# Sheet1.net
KiCad netlist of a schematic drawn in Altium Designer
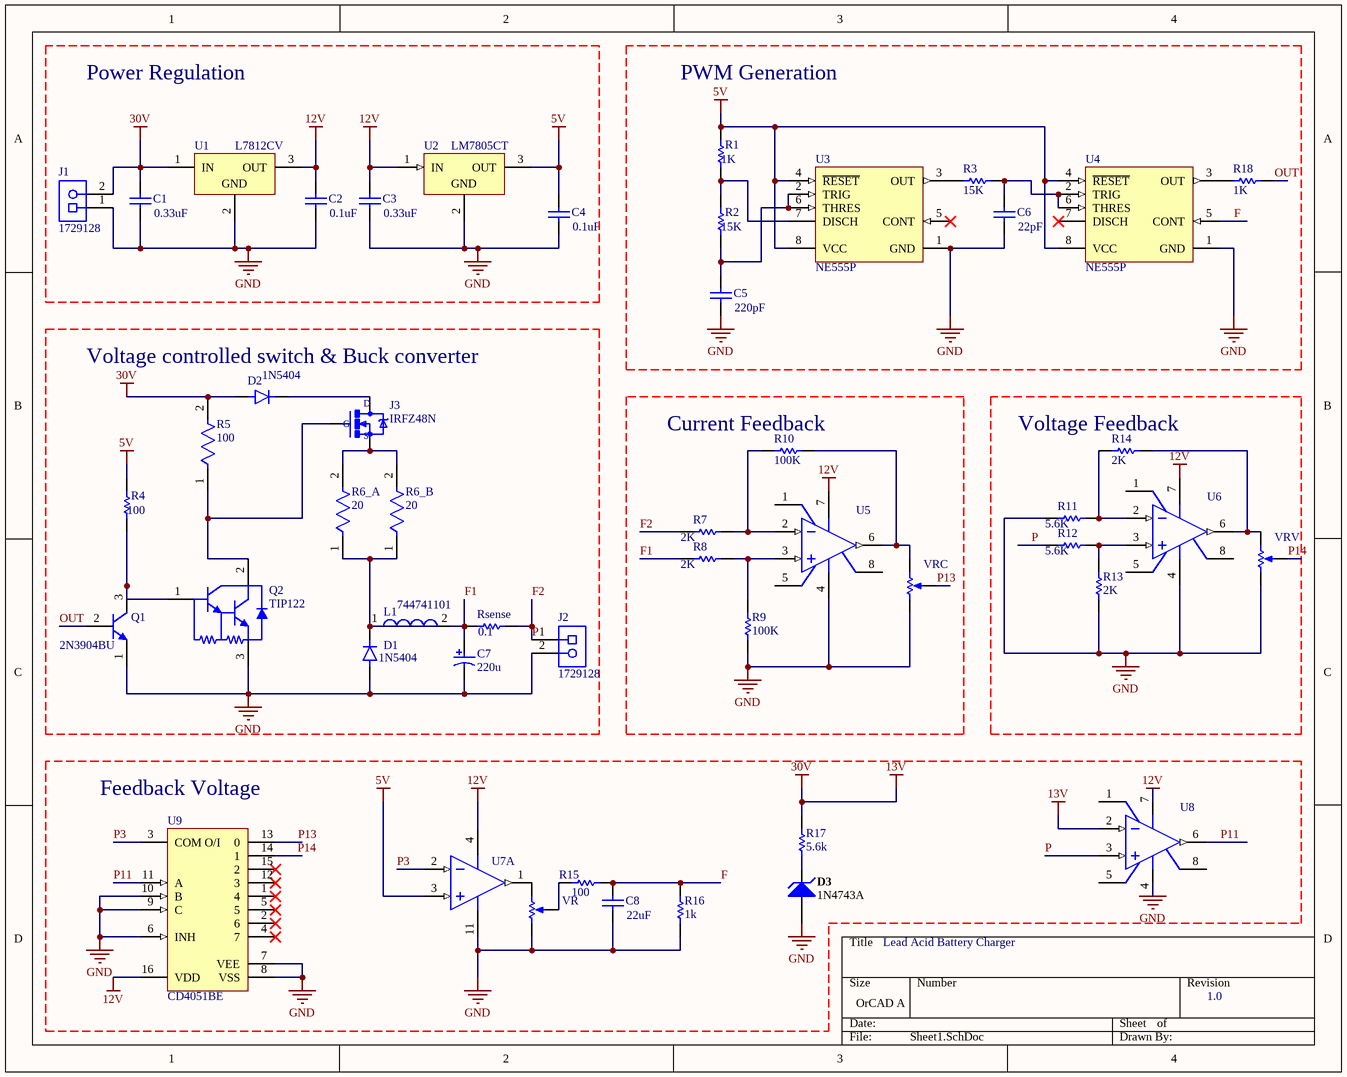
[diagram p0: Sheet1.SchDoc]

(export (version "E")
  (design (tool "Eeschema 10.0.6"))
  (components
    (comp (ref "C1")
      (value "0.33uF")
      (footprint "RAD-0.3")
      (description "Capacitor")
      (fields (field (name "Comment") "Cap") (field (name "PUBLISHER") "Altium Limited"))
      (libsource (lib "Miscellaneous Devices") (part "Cap"))
    )
    (comp (ref "C2")
      (value "0.1uF")
      (footprint "RAD-0.3")
      (description "Capacitor")
      (fields (field (name "Comment") "Cap") (field (name "PUBLISHER") "Altium Limited"))
      (libsource (lib "Miscellaneous Devices") (part "Cap"))
    )
    (comp (ref "C3")
      (value "0.33uF")
      (footprint "RAD-0.3")
      (description "Capacitor")
      (fields (field (name "Comment") "Cap") (field (name "PUBLISHER") "Altium Limited"))
      (libsource (lib "Miscellaneous Devices") (part "Cap"))
    )
    (comp (ref "C4")
      (value "0.1uF")
      (footprint "RAD-0.3")
      (description "Capacitor")
      (fields (field (name "Comment") "Cap") (field (name "PUBLISHER") "Altium Limited"))
      (libsource (lib "Miscellaneous Devices") (part "Cap"))
    )
    (comp (ref "C5")
      (value "220pF")
      (footprint "RAD-0.3")
      (description "Capacitor")
      (fields (field (name "Comment") "Cap") (field (name "PUBLISHER") "Altium Limited"))
      (libsource (lib "Miscellaneous Devices") (part "Cap"))
    )
    (comp (ref "C6")
      (value "22pF")
      (footprint "RAD-0.3")
      (description "Capacitor")
      (fields (field (name "Comment") "Cap") (field (name "PUBLISHER") "Altium Limited"))
      (libsource (lib "Miscellaneous Devices") (part "Cap"))
    )
    (comp (ref "C7")
      (value "220u")
      (footprint "PNSC-ECA-1VM221-2")
      (description "Aluminum Electrolytic Capacitor, 220 uF, +/- 20%, 35 V, -40 to 85 degC, 2-Pin THD, RoHS, Bulk")
      (fields (field (name "MANUFACTURER") "Panasonic"))
      (libsource (lib "Altium Content Vault") (part "CAP-P-2"))
    )
    (comp (ref "C8")
      (value "22uF")
      (footprint "RAD-0.3")
      (description "Capacitor")
      (fields (field (name "Comment") "Cap") (field (name "PUBLISHER") "Altium Limited"))
      (libsource (lib "Miscellaneous Devices") (part "Cap"))
    )
    (comp (ref "D1")
      (value "1N5404")
      (footprint "DIOAD1990W125L900D530")
      (fields (field (name "MP") "1N5404RL") (field (name "MF") "{'manufacturer': u'ON Semiconductor'}"))
      (libsource (lib "SnapEDA_Library") (part "1N5404RL"))
    )
    (comp (ref "D2")
      (value "1N5404")
      (footprint "DIOAD1990W125L900D530")
      (fields (field (name "MP") "1N5404RL") (field (name "MF") "{'manufacturer': u'ON Semiconductor'}"))
      (libsource (lib "SnapEDA_Library") (part "1N5404RL"))
    )
    (comp (ref "D3")
      (value "1N4743A")
      (footprint "FAIR-DO-41-2_V")
      (description "Zener Diode, 13V, 1W, 5%, -65 to 200 degC, 2-Pin DO-41, Body 2.72 x 5.2 mm, RoHS")
      (fields (field (name "MANUFACTURER") "Fairchild Semiconductor") (field (name "TOLERANCE") "5%"))
      (libsource (lib "Altium Content Vault") (part "FAIR-DZEN-A1K2-2"))
    )
    (comp (ref "J1")
      (value "1729128")
      (footprint "PHOE-1729128-2_V")
      (description "PCB Terminal Block, 13.5 A, 400 V, 2-Pin THD, RoHS, Bulk")
      (fields (field (name "MANUFACTURER") "Phoenix Contact"))
      (libsource (lib "") (part "CN-2P-F-R2_1"))
    )
    (comp (ref "J2")
      (value "1729128")
      (footprint "PHOE-1729128-2_V")
      (description "PCB Terminal Block, 13.5 A, 400 V, 2-Pin THD, RoHS, Bulk")
      (fields (field (name "MANUFACTURER") "Phoenix Contact"))
      (libsource (lib "Altium Content Vault") (part "CN-2P-F-R2"))
    )
    (comp (ref "J3")
      (value "IRFZ48N")
      (footprint "IRFZ44NPBF:TO-220")
      (fields (field (name "MF") "{'manufacturer': u'Infineon'}") (field (name "MP") "IRFZ44NPBF"))
      (libsource (lib "*") (part "IRFZ44NPBF"))
    )
    (comp (ref "L1")
      (value "744741101")
      (footprint "WE-TI-LS")
      (description "Radial Leaded Wire Wound Inductor WE-TI, L = 100 µH")
      (libsource (lib "Altium Content Vault") (part "PAS-IND-INDUCTOR-2"))
    )
    (comp (ref "Q1")
      (value "2N3904BU")
      (footprint "FAIR-TO-92")
      (description "NPN General-Purpose Amplifier, 40 V VCEO, 0.2 A, -55 to 150 degC, 2-Pin TO-92, RoHS, Bulk")
      (fields (field (name "MANUFACTURER") "FairchildSemiconductor"))
      (libsource (lib "Altium Content Vault") (part "NPN-E1B2C3-3"))
    )
    (comp (ref "Q2")
      (value "TIP122")
      (footprint "ONSC-TO-220-3-221A-09")
      (description "Plastic Medium-Power, Complementary Silicon Transistor, 3-Pin TO-220, Tube")
      (fields (field (name "MANUFACTURER") "On Semiconductor"))
      (libsource (lib "Altium Content Vault") (part "ONSC-DT-NPN-B1C2E3-3_A"))
    )
    (comp (ref "R1")
      (value "1K")
      (footprint "AXIAL-0.3")
      (description "Resistor")
      (fields (field (name "Comment") "Res1") (field (name "PUBLISHER") "Altium Limited"))
      (libsource (lib "Miscellaneous Devices") (part "Res1"))
    )
    (comp (ref "R2")
      (value "15K")
      (footprint "AXIAL-0.3")
      (description "Resistor")
      (fields (field (name "Comment") "Res1") (field (name "PUBLISHER") "Altium Limited"))
      (libsource (lib "Miscellaneous Devices") (part "Res1"))
    )
    (comp (ref "R3")
      (value "15K")
      (footprint "AXIAL-0.3")
      (description "Resistor")
      (fields (field (name "Comment") "Res1") (field (name "PUBLISHER") "Altium Limited"))
      (libsource (lib "Miscellaneous Devices") (part "Res1"))
    )
    (comp (ref "R4")
      (value "100")
      (footprint "AXIAL-0.3")
      (description "Resistor")
      (fields (field (name "Comment") "Res1") (field (name "PUBLISHER") "Altium Limited"))
      (libsource (lib "Miscellaneous Devices") (part "Res1"))
    )
    (comp (ref "R5")
      (value "100")
      (footprint "FP-SQP500-MFG")
      (description "RES 1.2 OHM 5W 5% AXIAL")
      (fields
        (field (name "MANUFACTURER PART NUMBER") "SQP500JB-1R2")
        (field (name "OCTOPART") "https://octopart.com/sqp500jb-1r2-yageo-1162571")
      )
      (libsource (lib "Altium Content Vault") (part "1029c3af85768c4190bb7ad29bc67b5"))
    )
    (comp (ref "R6_A")
      (value "20")
      (footprint "FP-SQP500-MFG")
      (description "RES 1.2 OHM 5W 5% AXIAL")
      (fields
        (field (name "MANUFACTURER PART NUMBER") "SQP500JB-1R2")
        (field (name "OCTOPART") "https://octopart.com/sqp500jb-1r2-yageo-1162571")
      )
      (libsource (lib "Altium Content Vault") (part "1029c3af85768c4190bb7ad29bc67b5"))
    )
    (comp (ref "R6_B")
      (value "20")
      (footprint "FP-SQP500-MFG")
      (description "RES 1.2 OHM 5W 5% AXIAL")
      (fields
        (field (name "MANUFACTURER PART NUMBER") "SQP500JB-1R2")
        (field (name "OCTOPART") "https://octopart.com/sqp500jb-1r2-yageo-1162571")
      )
      (libsource (lib "Altium Content Vault") (part "1029c3af85768c4190bb7ad29bc67b5"))
    )
    (comp (ref "R7")
      (value "2K")
      (footprint "AXIAL-0.3")
      (description "Resistor")
      (fields (field (name "Comment") "Res1") (field (name "PUBLISHER") "Altium Limited"))
      (libsource (lib "Miscellaneous Devices") (part "Res1"))
    )
    (comp (ref "R8")
      (value "2K")
      (footprint "AXIAL-0.3")
      (description "Resistor")
      (fields (field (name "Comment") "Res1") (field (name "PUBLISHER") "Altium Limited"))
      (libsource (lib "Miscellaneous Devices") (part "Res1"))
    )
    (comp (ref "R9")
      (value "100K")
      (footprint "AXIAL-0.3")
      (description "Resistor")
      (fields (field (name "Comment") "Res1") (field (name "PUBLISHER") "Altium Limited"))
      (libsource (lib "Miscellaneous Devices") (part "Res1"))
    )
    (comp (ref "R10")
      (value "100K")
      (footprint "AXIAL-0.3")
      (description "Resistor")
      (fields (field (name "Comment") "Res1") (field (name "PUBLISHER") "Altium Limited"))
      (libsource (lib "Miscellaneous Devices") (part "Res1"))
    )
    (comp (ref "R11")
      (value "5.6K")
      (footprint "AXIAL-0.3")
      (description "Resistor")
      (fields (field (name "Comment") "Res1") (field (name "PUBLISHER") "Altium Limited"))
      (libsource (lib "Miscellaneous Devices") (part "Res1"))
    )
    (comp (ref "R12")
      (value "5.6K")
      (footprint "AXIAL-0.3")
      (description "Resistor")
      (fields (field (name "Comment") "Res1") (field (name "PUBLISHER") "Altium Limited"))
      (libsource (lib "Miscellaneous Devices") (part "Res1"))
    )
    (comp (ref "R13")
      (value "2K")
      (footprint "AXIAL-0.3")
      (description "Resistor")
      (fields (field (name "Comment") "Res1") (field (name "PUBLISHER") "Altium Limited"))
      (libsource (lib "Miscellaneous Devices") (part "Res1"))
    )
    (comp (ref "R14")
      (value "2K")
      (footprint "AXIAL-0.3")
      (description "Resistor")
      (fields (field (name "Comment") "Res1") (field (name "PUBLISHER") "Altium Limited"))
      (libsource (lib "Miscellaneous Devices") (part "Res1"))
    )
    (comp (ref "R15")
      (value "100")
      (footprint "AXIAL-0.3")
      (description "Resistor")
      (fields (field (name "Comment") "Res1") (field (name "PUBLISHER") "Altium Limited"))
      (libsource (lib "Miscellaneous Devices") (part "Res1"))
    )
    (comp (ref "R16")
      (value "1k")
      (footprint "AXIAL-0.3")
      (description "Resistor")
      (fields (field (name "Comment") "Res1") (field (name "PUBLISHER") "Altium Limited"))
      (libsource (lib "Miscellaneous Devices") (part "Res1"))
    )
    (comp (ref "R17")
      (value "5.6k")
      (footprint "AXIAL-0.3")
      (description "Resistor")
      (fields (field (name "Comment") "Res1") (field (name "PUBLISHER") "Altium Limited"))
      (libsource (lib "Miscellaneous Devices") (part "Res1"))
    )
    (comp (ref "R18")
      (value "1K")
      (footprint "AXIAL-0.3")
      (description "Resistor")
      (fields (field (name "Comment") "Res1") (field (name "PUBLISHER") "Altium Limited"))
      (libsource (lib "Miscellaneous Devices") (part "Res1"))
    )
    (comp (ref "Rsense")
      (value "0.1")
      (footprint "AXIAL-0.3")
      (description "Resistor")
      (fields (field (name "Comment") "Res1") (field (name "PUBLISHER") "Altium Limited"))
      (libsource (lib "Miscellaneous Devices") (part "Res1"))
    )
    (comp (ref "U1")
      (value "L7812CV")
      (footprint "TO220")
      (description "Positive Voltage Regulator, 12V, 3-Pin TO-220")
      (libsource (lib "Altium Content Vault") (part "PM-REG-L4940-SIL3"))
    )
    (comp (ref "U2")
      (value "LM7805CT")
      (footprint "FAIR-TO-220-3")
      (description "Positive Voltage Regulator, 5 V, 1 A, -40 to 125 degC, 3-Pin TO-220, RoHS, Tube")
      (fields (field (name "MANUFACTURER") "FairchildSemiconductor"))
      (libsource (lib "Altium Content Vault") (part "FAIR-LM7805CT-TO220-3"))
    )
    (comp (ref "U3")
      (value "NE555P")
      (footprint "P0008A")
      (description "Precision Timer, 4.5 to 16 V, 0 to 70 degC, 8-Pin DIP, Pb-Free, Tube")
      (fields (field (name "MANUFACTURER") "TexasInstruments"))
      (libsource (lib "Altium Content Vault") (part "TI-NE555-P8"))
    )
    (comp (ref "U4")
      (value "NE555P")
      (footprint "P0008A")
      (description "Precision Timer, 4.5 to 16 V, 0 to 70 degC, 8-Pin DIP, Pb-Free, Tube")
      (fields (field (name "MANUFACTURER") "TexasInstruments"))
      (libsource (lib "Altium Content Vault") (part "TI-NE555-P8"))
    )
    (comp (ref "U5")
      (value "LM741CN/NOPB")
      (footprint "P0008A")
      (description "Operational Amplifier, 8-pin MDIP, Pb-Free")
      (fields (field (name "MANUFACTURER") "Texas Instruments"))
      (libsource (lib "Altium Content Vault") (part "AMP-OPA-LM741-8"))
    )
    (comp (ref "U6")
      (value "LM741CN/NOPB")
      (footprint "P0008A")
      (description "Operational Amplifier, 8-pin MDIP, Pb-Free")
      (fields (field (name "MANUFACTURER") "Texas Instruments"))
      (libsource (lib "Altium Content Vault") (part "AMP-OPA-LM741-8"))
    )
    (comp (ref "U7")
      (value "TL074ACN")
      (footprint "N0014A")
      (fields (field (name "MANUFACTURER") "Texas Instruments"))
      (libsource (lib "Altium Content Vault") (part "TI-TL074X-14"))
    )
    (comp (ref "U8")
      (value "LM741CN/NOPB")
      (footprint "P0008A")
      (description "Operational Amplifier, 8-pin MDIP, Pb-Free")
      (fields (field (name "MANUFACTURER") "Texas Instruments"))
      (libsource (lib "Altium Content Vault") (part "AMP-OPA-LM741-8"))
    )
    (comp (ref "U9")
      (value "CD4051BE")
      (footprint "N0016A")
      (description "CMOS Single 8-Channel Analog Multiplexer/Demultiplexer with Logic-Level Conversion, N0016A, TUBE")
      (fields
        (field (name "GENERIC PART NUMBER") "CD4051B")
        (field (name "MANUFACTURER") "Texas Instruments")
      )
      (libsource (lib "Altium Content Vault") (part "TI-CD4051B-16"))
    )
    (comp (ref "VR")
      (value "3362P-1-103LF")
      (footprint "BOUR-3362P")
      (description "Square Trimpot(R) Trimming Potentiometer, 10 KOhm, 300 V, -55 to 125 degC, 3-Pin THD, RoHS, Tube")
      (fields (field (name "TOLERANCE") "1%"))
      (libsource (lib "Altium Content Vault") (part "RES-POT-3"))
    )
    (comp (ref "VRC")
      (value "3362P-1-103LF")
      (footprint "BOUR-3362P")
      (description "Square Trimpot(R) Trimming Potentiometer, 10 KOhm, 300 V, -55 to 125 degC, 3-Pin THD, RoHS, Tube")
      (fields (field (name "TOLERANCE") "1%"))
      (libsource (lib "Altium Content Vault") (part "RES-POT-3"))
    )
    (comp (ref "VRV")
      (value "3362P-1-103LF")
      (footprint "BOUR-3362P")
      (description "Square Trimpot(R) Trimming Potentiometer, 10 KOhm, 300 V, -55 to 125 degC, 3-Pin THD, RoHS, Tube")
      (fields (field (name "TOLERANCE") "1%"))
      (libsource (lib "Altium Content Vault") (part "RES-POT-3"))
    )
  )
  (nets
    (net (code "1") (name "/F") (class "Default")
      (node (ref "C8") (pin "2") (pinfunction "2_2") (pintype "passive"))
      (node (ref "R15") (pin "1") (pinfunction "1_1") (pintype "passive"))
      (node (ref "R16") (pin "1") (pinfunction "1_1") (pintype "passive"))
      (node (ref "U4") (pin "5") (pinfunction "CONT_5") (pintype "input"))
    )
    (net (code "2") (name "/F1") (class "Default")
      (node (ref "C7") (pin "1") (pinfunction "1_1") (pintype "passive"))
      (node (ref "L1") (pin "2") (pinfunction "2_2") (pintype "passive"))
      (node (ref "R8") (pin "1") (pinfunction "1_1") (pintype "passive"))
      (node (ref "Rsense") (pin "1") (pinfunction "1_1") (pintype "passive"))
    )
    (net (code "3") (name "/F2") (class "Default")
      (node (ref "J2") (pin "1") (pinfunction "1_1") (pintype "passive"))
      (node (ref "R12") (pin "1") (pinfunction "1_1") (pintype "passive"))
      (node (ref "R7") (pin "1") (pinfunction "1_1") (pintype "passive"))
      (node (ref "Rsense") (pin "2") (pinfunction "2_2") (pintype "passive"))
      (node (ref "U8") (pin "3") (pinfunction "IN+_3") (pintype "input"))
    )
    (net (code "4") (name "/OUT") (class "Default")
      (node (ref "Q1") (pin "2") (pinfunction "B_2") (pintype "passive"))
      (node (ref "R18") (pin "1") (pinfunction "1_1") (pintype "passive"))
    )
    (net (code "5") (name "/P3") (class "Default")
      (node (ref "U7") (pin "2") (pinfunction "IN1-_2") (pintype "input"))
      (node (ref "U9") (pin "3") (pinfunction "COM_O/I_3") (pintype "passive"))
    )
    (net (code "6") (name "/P11") (class "Default")
      (node (ref "U8") (pin "6") (pinfunction "OUT_6") (pintype "output"))
      (node (ref "U9") (pin "11") (pinfunction "A_11") (pintype "input"))
    )
    (net (code "7") (name "/P13") (class "Default")
      (node (ref "U9") (pin "13") (pinfunction "0_13") (pintype "passive"))
      (node (ref "VRC") (pin "2") (pinfunction "S_2") (pintype "passive"))
    )
    (net (code "8") (name "/P14") (class "Default")
      (node (ref "U9") (pin "14") (pinfunction "1_14") (pintype "passive"))
      (node (ref "VRV") (pin "2") (pinfunction "S_2") (pintype "passive"))
    )
    (net (code "9") (name "5V") (class "Default")
      (node (ref "C4") (pin "2") (pinfunction "2_2") (pintype "passive"))
      (node (ref "R1") (pin "2") (pinfunction "2_2") (pintype "passive"))
      (node (ref "R4") (pin "2") (pinfunction "2_2") (pintype "passive"))
      (node (ref "U2") (pin "3") (pinfunction "OUT_3") (pintype "passive"))
      (node (ref "U3") (pin "4") (pinfunction "~{RESET}_4") (pintype "input"))
      (node (ref "U3") (pin "8") (pinfunction "VCC_8") (pintype "power_in"))
      (node (ref "U4") (pin "4") (pinfunction "~{RESET}_4") (pintype "input"))
      (node (ref "U4") (pin "8") (pinfunction "VCC_8") (pintype "power_in"))
      (node (ref "U7") (pin "3") (pinfunction "IN1+_3") (pintype "input"))
    )
    (net (code "10") (name "12V") (class "Default")
      (node (ref "C2") (pin "2") (pinfunction "2_2") (pintype "passive"))
      (node (ref "C3") (pin "2") (pinfunction "2_2") (pintype "passive"))
      (node (ref "U1") (pin "3") (pinfunction "OUT_3") (pintype "power_in"))
      (node (ref "U2") (pin "1") (pinfunction "IN_1") (pintype "input"))
      (node (ref "U5") (pin "7") (pinfunction "V+_7") (pintype "power_in"))
      (node (ref "U6") (pin "7") (pinfunction "V+_7") (pintype "power_in"))
      (node (ref "U7") (pin "4") (pinfunction "VCC+_4") (pintype "power_in"))
      (node (ref "U8") (pin "7") (pinfunction "V+_7") (pintype "power_in"))
      (node (ref "U9") (pin "16") (pinfunction "VDD_16") (pintype "power_in"))
    )
    (net (code "11") (name "13V") (class "Default")
      (node (ref "C1") (pin "2") (pinfunction "2_2") (pintype "passive"))
      (node (ref "D2") (pin "A") (pinfunction "A_A") (pintype "passive"))
      (node (ref "J1") (pin "2") (pinfunction "2_2") (pintype "passive"))
      (node (ref "R17") (pin "1") (pinfunction "1_1") (pintype "passive"))
      (node (ref "R5") (pin "2") (pinfunction "2_2") (pintype "passive"))
      (node (ref "U1") (pin "1") (pinfunction "IN_1") (pintype "power_in"))
      (node (ref "U8") (pin "2") (pinfunction "IN-_2") (pintype "input"))
    )
    (net (code "12") (name "GND") (class "Default")
      (node (ref "C1") (pin "1") (pinfunction "1_1") (pintype "passive"))
      (node (ref "C2") (pin "1") (pinfunction "1_1") (pintype "passive"))
      (node (ref "C3") (pin "1") (pinfunction "1_1") (pintype "passive"))
      (node (ref "C4") (pin "1") (pinfunction "1_1") (pintype "passive"))
      (node (ref "C5") (pin "1") (pinfunction "1_1") (pintype "passive"))
      (node (ref "C6") (pin "1") (pinfunction "1_1") (pintype "passive"))
      (node (ref "C7") (pin "2") (pinfunction "2_2") (pintype "passive"))
      (node (ref "C8") (pin "1") (pinfunction "1_1") (pintype "passive"))
      (node (ref "D1") (pin "A") (pinfunction "A_A") (pintype "passive"))
      (node (ref "D3") (pin "1") (pinfunction "A_1") (pintype "passive"))
      (node (ref "J1") (pin "1") (pinfunction "1_1") (pintype "passive"))
      (node (ref "J2") (pin "2") (pinfunction "2_2") (pintype "passive"))
      (node (ref "Q1") (pin "1") (pinfunction "E_1") (pintype "passive"))
      (node (ref "Q2") (pin "3") (pinfunction "E_3") (pintype "passive"))
      (node (ref "R11") (pin "1") (pinfunction "1_1") (pintype "passive"))
      (node (ref "R13") (pin "1") (pinfunction "1_1") (pintype "passive"))
      (node (ref "R16") (pin "2") (pinfunction "2_2") (pintype "passive"))
      (node (ref "R9") (pin "1") (pinfunction "1_1") (pintype "passive"))
      (node (ref "U1") (pin "2") (pinfunction "GND_2") (pintype "power_in"))
      (node (ref "U2") (pin "2") (pinfunction "GND_2") (pintype "power_in"))
      (node (ref "U3") (pin "1") (pinfunction "GND_1") (pintype "power_in"))
      (node (ref "U4") (pin "1") (pinfunction "GND_1") (pintype "power_in"))
      (node (ref "U5") (pin "4") (pinfunction "V-_4") (pintype "power_in"))
      (node (ref "U6") (pin "4") (pinfunction "V-_4") (pintype "power_in"))
      (node (ref "U7") (pin "11") (pinfunction "VCC-_11") (pintype "power_in"))
      (node (ref "U8") (pin "4") (pinfunction "V-_4") (pintype "power_in"))
      (node (ref "U9") (pin "10") (pinfunction "B_10") (pintype "input"))
      (node (ref "U9") (pin "6") (pinfunction "INH_6") (pintype "input"))
      (node (ref "U9") (pin "7") (pinfunction "VEE_7") (pintype "power_in"))
      (node (ref "U9") (pin "8") (pinfunction "VSS_8") (pintype "power_in"))
      (node (ref "U9") (pin "9") (pinfunction "C_9") (pintype "input"))
      (node (ref "VR") (pin "1") (pinfunction "CCW_1") (pintype "passive"))
      (node (ref "VRC") (pin "1") (pinfunction "CCW_1") (pintype "passive"))
      (node (ref "VRV") (pin "1") (pinfunction "CCW_1") (pintype "passive"))
    )
    (net (code "13") (name "Net-(D1-K)") (class "Default")
      (node (ref "D1") (pin "C") (pinfunction "K_C") (pintype "passive"))
      (node (ref "L1") (pin "1") (pinfunction "1_1") (pintype "passive"))
      (node (ref "R6_A") (pin "1") (pinfunction "1_1") (pintype "passive"))
      (node (ref "R6_B") (pin "1") (pinfunction "1_1") (pintype "passive"))
    )
    (net (code "14") (name "Net-(D2-K)") (class "Default")
      (node (ref "D2") (pin "C") (pinfunction "K_C") (pintype "passive"))
      (node (ref "J3") (pin "2") (pinfunction "D_2") (pintype "passive"))
    )
    (net (code "15") (name "Net-(D3-K)") (class "Default")
      (node (ref "D3") (pin "2") (pinfunction "K_2") (pintype "passive"))
      (node (ref "R17") (pin "2") (pinfunction "2_2") (pintype "passive"))
    )
    (net (code "16") (name "Net-(J3-G)") (class "Default")
      (node (ref "J3") (pin "1") (pinfunction "G_1") (pintype "passive"))
      (node (ref "Q2") (pin "2") (pinfunction "C_2") (pintype "passive"))
      (node (ref "R5") (pin "1") (pinfunction "1_1") (pintype "passive"))
    )
    (net (code "17") (name "Net-(J3-S)") (class "Default")
      (node (ref "J3") (pin "3") (pinfunction "S_3") (pintype "passive"))
      (node (ref "R6_A") (pin "2") (pinfunction "2_2") (pintype "passive"))
      (node (ref "R6_B") (pin "2") (pinfunction "2_2") (pintype "passive"))
    )
    (net (code "18") (name "Net-(Q1-C)") (class "Default")
      (node (ref "Q1") (pin "3") (pinfunction "C_3") (pintype "passive"))
      (node (ref "Q2") (pin "1") (pinfunction "B_1") (pintype "passive"))
      (node (ref "R4") (pin "1") (pinfunction "1_1") (pintype "passive"))
    )
    (net (code "19") (name "Net-(U3-DISCH)") (class "Default")
      (node (ref "R1") (pin "1") (pinfunction "1_1") (pintype "passive"))
      (node (ref "R2") (pin "2") (pinfunction "2_2") (pintype "passive"))
      (node (ref "U3") (pin "7") (pinfunction "DISCH_7") (pintype "open_collector"))
    )
    (net (code "20") (name "Net-(U3-OUT)") (class "Default")
      (node (ref "R3") (pin "2") (pinfunction "2_2") (pintype "passive"))
      (node (ref "U3") (pin "3") (pinfunction "OUT_3") (pintype "output"))
    )
    (net (code "21") (name "Net-(U3-THRES)") (class "Default")
      (node (ref "C5") (pin "2") (pinfunction "2_2") (pintype "passive"))
      (node (ref "R2") (pin "1") (pinfunction "1_1") (pintype "passive"))
      (node (ref "U3") (pin "2") (pinfunction "TRIG_2") (pintype "input"))
      (node (ref "U3") (pin "6") (pinfunction "THRES_6") (pintype "input"))
    )
    (net (code "22") (name "Net-(U4-OUT)") (class "Default")
      (node (ref "R18") (pin "2") (pinfunction "2_2") (pintype "passive"))
      (node (ref "U4") (pin "3") (pinfunction "OUT_3") (pintype "output"))
    )
    (net (code "23") (name "Net-(U4-THRES)") (class "Default")
      (node (ref "C6") (pin "2") (pinfunction "2_2") (pintype "passive"))
      (node (ref "R3") (pin "1") (pinfunction "1_1") (pintype "passive"))
      (node (ref "U4") (pin "2") (pinfunction "TRIG_2") (pintype "input"))
      (node (ref "U4") (pin "6") (pinfunction "THRES_6") (pintype "input"))
    )
    (net (code "24") (name "Net-(U5-IN+)") (class "Default")
      (node (ref "R8") (pin "2") (pinfunction "2_2") (pintype "passive"))
      (node (ref "R9") (pin "2") (pinfunction "2_2") (pintype "passive"))
      (node (ref "U5") (pin "3") (pinfunction "IN+_3") (pintype "input"))
    )
    (net (code "25") (name "Net-(U5-IN-)") (class "Default")
      (node (ref "R10") (pin "2") (pinfunction "2_2") (pintype "passive"))
      (node (ref "R7") (pin "2") (pinfunction "2_2") (pintype "passive"))
      (node (ref "U5") (pin "2") (pinfunction "IN-_2") (pintype "input"))
    )
    (net (code "26") (name "Net-(U5-OUT)") (class "Default")
      (node (ref "R10") (pin "1") (pinfunction "1_1") (pintype "passive"))
      (node (ref "U5") (pin "6") (pinfunction "OUT_6") (pintype "output"))
      (node (ref "VRC") (pin "3") (pinfunction "CW_3") (pintype "passive"))
    )
    (net (code "27") (name "Net-(U6-IN+)") (class "Default")
      (node (ref "R12") (pin "2") (pinfunction "2_2") (pintype "passive"))
      (node (ref "R13") (pin "2") (pinfunction "2_2") (pintype "passive"))
      (node (ref "U6") (pin "3") (pinfunction "IN+_3") (pintype "input"))
    )
    (net (code "28") (name "Net-(U6-IN-)") (class "Default")
      (node (ref "R11") (pin "2") (pinfunction "2_2") (pintype "passive"))
      (node (ref "R14") (pin "2") (pinfunction "2_2") (pintype "passive"))
      (node (ref "U6") (pin "2") (pinfunction "IN-_2") (pintype "input"))
    )
    (net (code "29") (name "Net-(U6-OUT)") (class "Default")
      (node (ref "R14") (pin "1") (pinfunction "1_1") (pintype "passive"))
      (node (ref "U6") (pin "6") (pinfunction "OUT_6") (pintype "output"))
      (node (ref "VRV") (pin "3") (pinfunction "CW_3") (pintype "passive"))
    )
    (net (code "30") (name "Net-(U7A-OUT1)") (class "Default")
      (node (ref "U7") (pin "1") (pinfunction "OUT1_1") (pintype "output"))
      (node (ref "VR") (pin "3") (pinfunction "CW_3") (pintype "passive"))
    )
    (net (code "31") (name "Net-(VR-S)") (class "Default")
      (node (ref "R15") (pin "2") (pinfunction "2_2") (pintype "passive"))
      (node (ref "VR") (pin "2") (pinfunction "S_2") (pintype "passive"))
    )
    (net (code "32") (name "unconnected-(U3-CONT-Pad5)") (class "Default")
      (node (ref "U3") (pin "5") (pinfunction "CONT_5") (pintype "input+no_connect"))
    )
    (net (code "33") (name "unconnected-(U4-DISCH-Pad7)") (class "Default")
      (node (ref "U4") (pin "7") (pinfunction "DISCH_7") (pintype "open_collector+no_connect"))
    )
    (net (code "34") (name "unconnected-(U5-NC-Pad8)") (class "Default")
      (node (ref "U5") (pin "8") (pinfunction "NC_8") (pintype "passive"))
    )
    (net (code "35") (name "unconnected-(U5-OFS_NULL-Pad1)") (class "Default")
      (node (ref "U5") (pin "1") (pinfunction "OFS_NULL_1") (pintype "passive"))
    )
    (net (code "36") (name "unconnected-(U5-OFS_NULL-Pad5)") (class "Default")
      (node (ref "U5") (pin "5") (pinfunction "OFS_NULL_5") (pintype "passive"))
    )
    (net (code "37") (name "unconnected-(U6-NC-Pad8)") (class "Default")
      (node (ref "U6") (pin "8") (pinfunction "NC_8") (pintype "passive"))
    )
    (net (code "38") (name "unconnected-(U6-OFS_NULL-Pad1)") (class "Default")
      (node (ref "U6") (pin "1") (pinfunction "OFS_NULL_1") (pintype "passive"))
    )
    (net (code "39") (name "unconnected-(U6-OFS_NULL-Pad5)") (class "Default")
      (node (ref "U6") (pin "5") (pinfunction "OFS_NULL_5") (pintype "passive"))
    )
    (net (code "40") (name "unconnected-(U8-NC-Pad8)") (class "Default")
      (node (ref "U8") (pin "8") (pinfunction "NC_8") (pintype "passive"))
    )
    (net (code "41") (name "unconnected-(U8-OFS_NULL-Pad1)") (class "Default")
      (node (ref "U8") (pin "1") (pinfunction "OFS_NULL_1") (pintype "passive"))
    )
    (net (code "42") (name "unconnected-(U8-OFS_NULL-Pad5)") (class "Default")
      (node (ref "U8") (pin "5") (pinfunction "OFS_NULL_5") (pintype "passive"))
    )
    (net (code "43") (name "unconnected-(U9-2-Pad15)") (class "Default")
      (node (ref "U9") (pin "15") (pinfunction "2_15") (pintype "passive+no_connect"))
    )
    (net (code "44") (name "unconnected-(U9-3-Pad12)") (class "Default")
      (node (ref "U9") (pin "12") (pinfunction "3_12") (pintype "passive+no_connect"))
    )
    (net (code "45") (name "unconnected-(U9-4-Pad1)") (class "Default")
      (node (ref "U9") (pin "1") (pinfunction "4_1") (pintype "passive+no_connect"))
    )
    (net (code "46") (name "unconnected-(U9-6-Pad2)") (class "Default")
      (node (ref "U9") (pin "2") (pinfunction "6_2") (pintype "passive+no_connect"))
    )
    (net (code "47") (name "unconnected-(U9-7-Pad4)") (class "Default")
      (node (ref "U9") (pin "4") (pinfunction "7_4") (pintype "passive+no_connect"))
    )
    (net (code "48") (name "unconnected-(U9-Pad5)") (class "Default")
      (node (ref "U9") (pin "5") (pinfunction "5_5") (pintype "passive+no_connect"))
    )
  )
)
